# TempSensors.net
KiCad netlist of a schematic drawn in Altium Designer
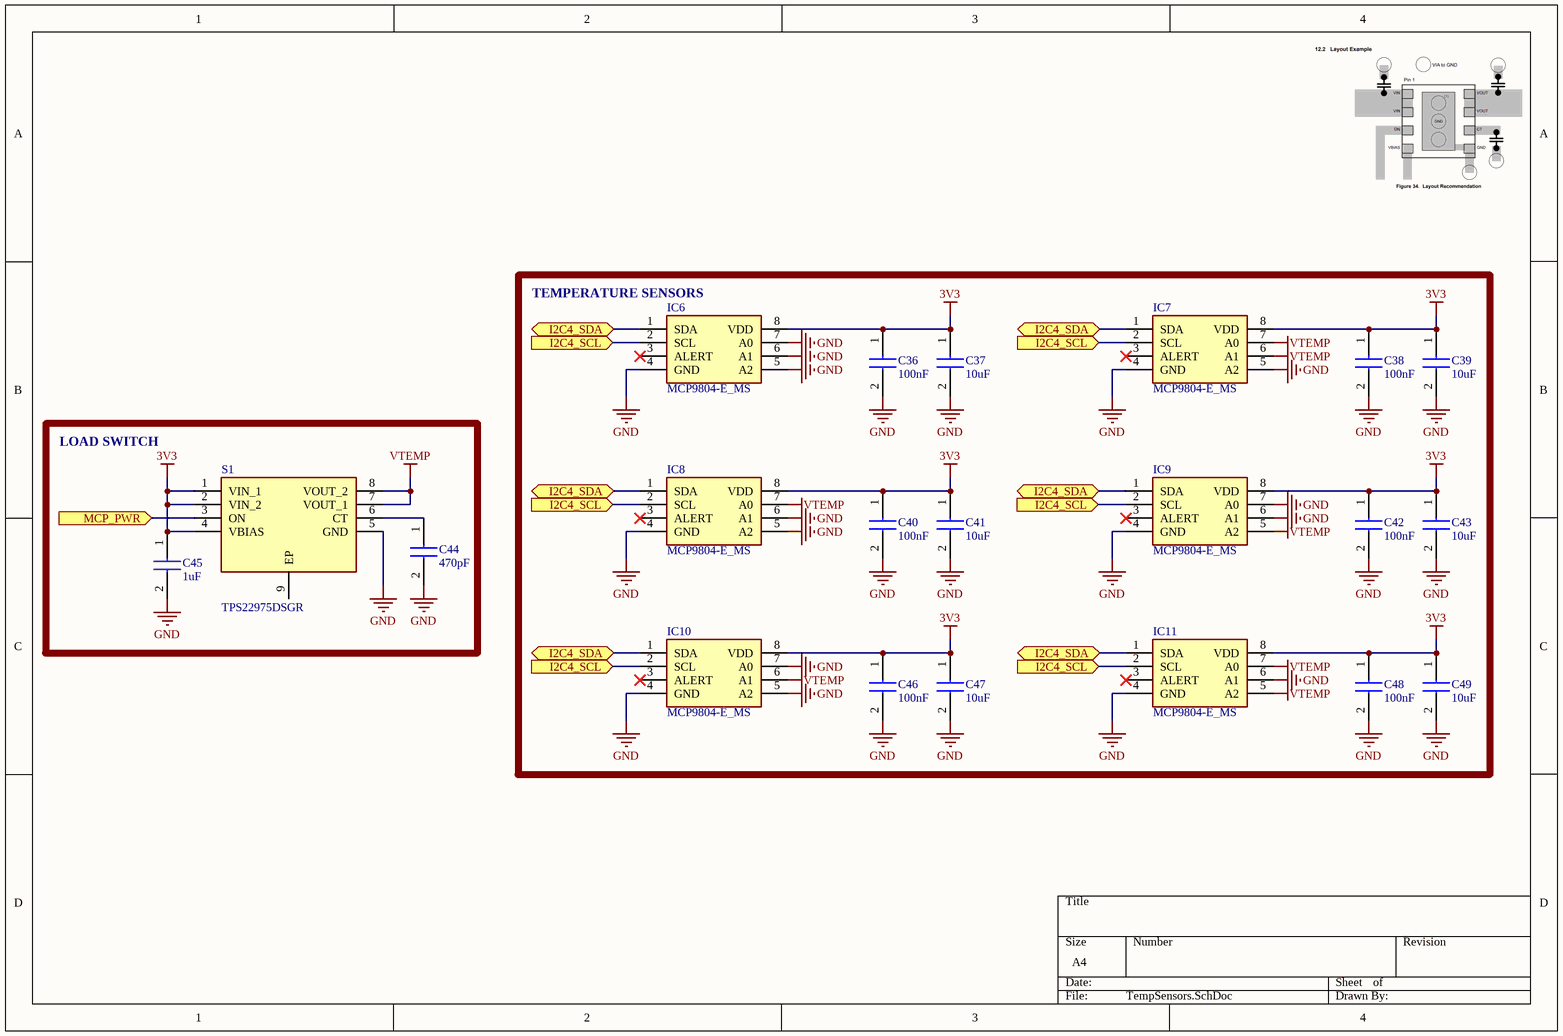
[diagram p0: TempSensors.SchDoc]

(export (version "E")
  (design (tool "Eeschema 10.0.6"))
  (components
    (comp (ref "C36")
      (value "100nF")
      (footprint "RT_IS:CAPC1608X95N")
      (description "0.1 µF ±20% 16V Ceramic Capacitor X7R 0603 (1608 Metric)")
      (fields (field (name "MANUFACTURER_PART_NUMBER") "C0603C104M4RAC7867"))
      (libsource (lib "*") (part "C0603C104M4RAC7867"))
    )
    (comp (ref "C37")
      (value "10uF")
      (footprint "RT_IS:CAPC1608X90N")
      (description "CAP CER 10UF 10V X7T 0603")
      (fields
        (field (name "MANUFACTURER_PART_NUMBER") "GRM188D71A106KA73D")
        (field (name "MOUSER PART NUMBER") "81-GRM188D71A106KA3D")
      )
      (libsource (lib "*") (part "GRM188D71A106KA73D"))
    )
    (comp (ref "C38")
      (value "100nF")
      (footprint "RT_IS:CAPC1608X95N")
      (description "0.1 µF ±20% 16V Ceramic Capacitor X7R 0603 (1608 Metric)")
      (fields (field (name "MANUFACTURER_PART_NUMBER") "C0603C104M4RAC7867"))
      (libsource (lib "*") (part "C0603C104M4RAC7867"))
    )
    (comp (ref "C39")
      (value "10uF")
      (footprint "RT_IS:CAPC1608X90N")
      (description "CAP CER 10UF 10V X7T 0603")
      (fields
        (field (name "MANUFACTURER_PART_NUMBER") "GRM188D71A106KA73D")
        (field (name "MOUSER PART NUMBER") "81-GRM188D71A106KA3D")
      )
      (libsource (lib "*") (part "GRM188D71A106KA73D"))
    )
    (comp (ref "C40")
      (value "100nF")
      (footprint "RT_IS:CAPC1608X95N")
      (description "0.1 µF ±20% 16V Ceramic Capacitor X7R 0603 (1608 Metric)")
      (fields (field (name "MANUFACTURER_PART_NUMBER") "C0603C104M4RAC7867"))
      (libsource (lib "*") (part "C0603C104M4RAC7867"))
    )
    (comp (ref "C41")
      (value "10uF")
      (footprint "RT_IS:CAPC1608X90N")
      (description "CAP CER 10UF 10V X7T 0603")
      (fields
        (field (name "MANUFACTURER_PART_NUMBER") "GRM188D71A106KA73D")
        (field (name "MOUSER PART NUMBER") "81-GRM188D71A106KA3D")
      )
      (libsource (lib "*") (part "GRM188D71A106KA73D"))
    )
    (comp (ref "C42")
      (value "100nF")
      (footprint "RT_IS:CAPC1608X95N")
      (description "0.1 µF ±20% 16V Ceramic Capacitor X7R 0603 (1608 Metric)")
      (fields (field (name "MANUFACTURER_PART_NUMBER") "C0603C104M4RAC7867"))
      (libsource (lib "*") (part "C0603C104M4RAC7867"))
    )
    (comp (ref "C43")
      (value "10uF")
      (footprint "RT_IS:CAPC1608X90N")
      (description "CAP CER 10UF 10V X7T 0603")
      (fields
        (field (name "MANUFACTURER_PART_NUMBER") "GRM188D71A106KA73D")
        (field (name "MOUSER PART NUMBER") "81-GRM188D71A106KA3D")
      )
      (libsource (lib "*") (part "GRM188D71A106KA73D"))
    )
    (comp (ref "C44")
      (value "470pF")
      (footprint "RT_IS:CAPC1608X87N")
      (description "CAP CER 470PF 50V X7R 0603")
      (fields (field (name "MANUFACTURER_PART_NUMBER") "0603B471K500CT"))
      (libsource (lib "*") (part "0603B471K500CT"))
    )
    (comp (ref "C45")
      (value "1uF")
      (footprint "RT_IS:CAPC1608X90N")
      (description "1 µF ±10% 25V Ceramic Capacitor X5R 0603 (1608 Metric)")
      (fields
        (field (name "MANUFACTURER_PART_NUMBER") "CL10A105KA8NNNC")
        (field (name "MOUSER PART NUMBER") "187-CL10A105KA8NNNC")
      )
      (libsource (lib "*") (part "CL10A105KA8NNNC"))
    )
    (comp (ref "C46")
      (value "100nF")
      (footprint "RT_IS:CAPC1608X95N")
      (description "0.1 µF ±20% 16V Ceramic Capacitor X7R 0603 (1608 Metric)")
      (fields (field (name "MANUFACTURER_PART_NUMBER") "C0603C104M4RAC7867"))
      (libsource (lib "*") (part "C0603C104M4RAC7867"))
    )
    (comp (ref "C47")
      (value "10uF")
      (footprint "RT_IS:CAPC1608X90N")
      (description "CAP CER 10UF 10V X7T 0603")
      (fields
        (field (name "MANUFACTURER_PART_NUMBER") "GRM188D71A106KA73D")
        (field (name "MOUSER PART NUMBER") "81-GRM188D71A106KA3D")
      )
      (libsource (lib "*") (part "GRM188D71A106KA73D"))
    )
    (comp (ref "C48")
      (value "100nF")
      (footprint "RT_IS:CAPC1608X95N")
      (description "0.1 µF ±20% 16V Ceramic Capacitor X7R 0603 (1608 Metric)")
      (fields (field (name "MANUFACTURER_PART_NUMBER") "C0603C104M4RAC7867"))
      (libsource (lib "*") (part "C0603C104M4RAC7867"))
    )
    (comp (ref "C49")
      (value "10uF")
      (footprint "RT_IS:CAPC1608X90N")
      (description "CAP CER 10UF 10V X7T 0603")
      (fields
        (field (name "MANUFACTURER_PART_NUMBER") "GRM188D71A106KA73D")
        (field (name "MOUSER PART NUMBER") "81-GRM188D71A106KA3D")
      )
      (libsource (lib "*") (part "GRM188D71A106KA73D"))
    )
    (comp (ref "IC6")
      (value "MCP9804-E_MS")
      (footprint "RT_IS:SOP65P490X110-8N")
      (description "Temperature Sensor Digital, Local -40°C ~ 125°C 10 b 8-MSOP")
      (fields
        (field (name "MANUFACTURER_PART_NUMBER") "MCP9804-E/MS")
        (field (name "MOUSER PART NUMBER") "579-MCP9804-E/MS")
      )
      (libsource (lib "*") (part "MCP9804-E_MS"))
    )
    (comp (ref "IC7")
      (value "MCP9804-E_MS")
      (footprint "RT_IS:SOP65P490X110-8N")
      (description "Temperature Sensor Digital, Local -40°C ~ 125°C 10 b 8-MSOP")
      (fields
        (field (name "MANUFACTURER_PART_NUMBER") "MCP9804-E/MS")
        (field (name "MOUSER PART NUMBER") "579-MCP9804-E/MS")
      )
      (libsource (lib "*") (part "MCP9804-E_MS"))
    )
    (comp (ref "IC8")
      (value "MCP9804-E_MS")
      (footprint "RT_IS:SOP65P490X110-8N")
      (description "Temperature Sensor Digital, Local -40°C ~ 125°C 10 b 8-MSOP")
      (fields
        (field (name "MANUFACTURER_PART_NUMBER") "MCP9804-E/MS")
        (field (name "MOUSER PART NUMBER") "579-MCP9804-E/MS")
      )
      (libsource (lib "*") (part "MCP9804-E_MS"))
    )
    (comp (ref "IC9")
      (value "MCP9804-E_MS")
      (footprint "RT_IS:SOP65P490X110-8N")
      (description "Temperature Sensor Digital, Local -40°C ~ 125°C 10 b 8-MSOP")
      (fields
        (field (name "MANUFACTURER_PART_NUMBER") "MCP9804-E/MS")
        (field (name "MOUSER PART NUMBER") "579-MCP9804-E/MS")
      )
      (libsource (lib "*") (part "MCP9804-E_MS"))
    )
    (comp (ref "IC10")
      (value "MCP9804-E_MS")
      (footprint "RT_IS:SOP65P490X110-8N")
      (description "Temperature Sensor Digital, Local -40°C ~ 125°C 10 b 8-MSOP")
      (fields
        (field (name "MANUFACTURER_PART_NUMBER") "MCP9804-E/MS")
        (field (name "MOUSER PART NUMBER") "579-MCP9804-E/MS")
      )
      (libsource (lib "*") (part "MCP9804-E_MS"))
    )
    (comp (ref "IC11")
      (value "MCP9804-E_MS")
      (footprint "RT_IS:SOP65P490X110-8N")
      (description "Temperature Sensor Digital, Local -40°C ~ 125°C 10 b 8-MSOP")
      (fields
        (field (name "MANUFACTURER_PART_NUMBER") "MCP9804-E/MS")
        (field (name "MOUSER PART NUMBER") "579-MCP9804-E/MS")
      )
      (libsource (lib "*") (part "MCP9804-E_MS"))
    )
    (comp (ref "S1")
      (value "TPS22975DSGR")
      (footprint "RT_IS:SON50P200X200X80-9N")
      (description "Power Switch/Driver 1:1 N-Channel 6A 8-WSON (2x2)")
      (fields (field (name "MOUSER PART NUMBER") "595-TPS22975DSGR"))
      (libsource (lib "*") (part "TPS22975DSGR"))
    )
  )
  (nets
    (net (code "1") (name "/I2C4_SCL") (class "Default")
      (node (ref "IC10") (pin "2") (pinfunction "SCL_2") (pintype "passive"))
      (node (ref "IC11") (pin "2") (pinfunction "SCL_2") (pintype "passive"))
      (node (ref "IC6") (pin "2") (pinfunction "SCL_2") (pintype "passive"))
      (node (ref "IC7") (pin "2") (pinfunction "SCL_2") (pintype "passive"))
      (node (ref "IC8") (pin "2") (pinfunction "SCL_2") (pintype "passive"))
    )
    (net (code "2") (name "/I2C4_SDA") (class "Default")
      (node (ref "IC10") (pin "1") (pinfunction "SDA_1") (pintype "passive"))
      (node (ref "IC11") (pin "1") (pinfunction "SDA_1") (pintype "passive"))
      (node (ref "IC6") (pin "1") (pinfunction "SDA_1") (pintype "passive"))
      (node (ref "IC7") (pin "1") (pinfunction "SDA_1") (pintype "passive"))
      (node (ref "IC8") (pin "1") (pinfunction "SDA_1") (pintype "passive"))
    )
    (net (code "3") (name "/MCP_PWR") (class "Default")
      (node (ref "S1") (pin "3") (pinfunction "ON_3") (pintype "passive"))
    )
    (net (code "4") (name "3V3") (class "Default")
      (node (ref "C36") (pin "1") (pinfunction "1_1") (pintype "passive"))
      (node (ref "C37") (pin "1") (pinfunction "1_1") (pintype "passive"))
      (node (ref "C38") (pin "1") (pinfunction "1_1") (pintype "passive"))
      (node (ref "C39") (pin "1") (pinfunction "1_1") (pintype "passive"))
      (node (ref "C40") (pin "1") (pinfunction "1_1") (pintype "passive"))
      (node (ref "C41") (pin "1") (pinfunction "1_1") (pintype "passive"))
      (node (ref "C42") (pin "1") (pinfunction "1_1") (pintype "passive"))
      (node (ref "C43") (pin "1") (pinfunction "1_1") (pintype "passive"))
      (node (ref "C45") (pin "1") (pinfunction "1_1") (pintype "passive"))
      (node (ref "C46") (pin "1") (pinfunction "1_1") (pintype "passive"))
      (node (ref "C47") (pin "1") (pinfunction "1_1") (pintype "passive"))
      (node (ref "C48") (pin "1") (pinfunction "1_1") (pintype "passive"))
      (node (ref "C49") (pin "1") (pinfunction "1_1") (pintype "passive"))
      (node (ref "IC10") (pin "8") (pinfunction "VDD_8") (pintype "passive"))
      (node (ref "IC11") (pin "8") (pinfunction "VDD_8") (pintype "passive"))
      (node (ref "IC6") (pin "8") (pinfunction "VDD_8") (pintype "passive"))
      (node (ref "IC7") (pin "8") (pinfunction "VDD_8") (pintype "passive"))
      (node (ref "IC8") (pin "8") (pinfunction "VDD_8") (pintype "passive"))
      (node (ref "IC9") (pin "8") (pinfunction "VDD_8") (pintype "passive"))
      (node (ref "S1") (pin "1") (pinfunction "VIN_1_1") (pintype "passive"))
      (node (ref "S1") (pin "2") (pinfunction "VIN_2_2") (pintype "passive"))
      (node (ref "S1") (pin "4") (pinfunction "VBIAS_4") (pintype "passive"))
    )
    (net (code "5") (name "GND") (class "Default")
      (node (ref "C36") (pin "2") (pinfunction "2_2") (pintype "passive"))
      (node (ref "C37") (pin "2") (pinfunction "2_2") (pintype "passive"))
      (node (ref "C38") (pin "2") (pinfunction "2_2") (pintype "passive"))
      (node (ref "C39") (pin "2") (pinfunction "2_2") (pintype "passive"))
      (node (ref "C40") (pin "2") (pinfunction "2_2") (pintype "passive"))
      (node (ref "C41") (pin "2") (pinfunction "2_2") (pintype "passive"))
      (node (ref "C42") (pin "2") (pinfunction "2_2") (pintype "passive"))
      (node (ref "C43") (pin "2") (pinfunction "2_2") (pintype "passive"))
      (node (ref "C44") (pin "2") (pinfunction "2_2") (pintype "passive"))
      (node (ref "C45") (pin "2") (pinfunction "2_2") (pintype "passive"))
      (node (ref "C46") (pin "2") (pinfunction "2_2") (pintype "passive"))
      (node (ref "C47") (pin "2") (pinfunction "2_2") (pintype "passive"))
      (node (ref "C48") (pin "2") (pinfunction "2_2") (pintype "passive"))
      (node (ref "C49") (pin "2") (pinfunction "2_2") (pintype "passive"))
      (node (ref "IC10") (pin "4") (pinfunction "GND_4") (pintype "passive"))
      (node (ref "IC10") (pin "5") (pinfunction "A2_5") (pintype "passive"))
      (node (ref "IC10") (pin "7") (pinfunction "A0_7") (pintype "passive"))
      (node (ref "IC11") (pin "4") (pinfunction "GND_4") (pintype "passive"))
      (node (ref "IC11") (pin "6") (pinfunction "A1_6") (pintype "passive"))
      (node (ref "IC6") (pin "4") (pinfunction "GND_4") (pintype "passive"))
      (node (ref "IC6") (pin "5") (pinfunction "A2_5") (pintype "passive"))
      (node (ref "IC6") (pin "6") (pinfunction "A1_6") (pintype "passive"))
      (node (ref "IC6") (pin "7") (pinfunction "A0_7") (pintype "passive"))
      (node (ref "IC7") (pin "4") (pinfunction "GND_4") (pintype "passive"))
      (node (ref "IC7") (pin "5") (pinfunction "A2_5") (pintype "passive"))
      (node (ref "IC8") (pin "4") (pinfunction "GND_4") (pintype "passive"))
      (node (ref "IC8") (pin "5") (pinfunction "A2_5") (pintype "passive"))
      (node (ref "IC8") (pin "6") (pinfunction "A1_6") (pintype "passive"))
      (node (ref "IC9") (pin "4") (pinfunction "GND_4") (pintype "passive"))
      (node (ref "IC9") (pin "6") (pinfunction "A1_6") (pintype "passive"))
      (node (ref "IC9") (pin "7") (pinfunction "A0_7") (pintype "passive"))
      (node (ref "S1") (pin "5") (pinfunction "GND_5") (pintype "passive"))
    )
    (net (code "6") (name "Net-(S1-CT)") (class "Default")
      (node (ref "C44") (pin "1") (pinfunction "1_1") (pintype "passive"))
      (node (ref "S1") (pin "6") (pinfunction "CT_6") (pintype "passive"))
    )
    (net (code "7") (name "VTEMP") (class "Default")
      (node (ref "IC10") (pin "6") (pinfunction "A1_6") (pintype "passive"))
      (node (ref "IC11") (pin "5") (pinfunction "A2_5") (pintype "passive"))
      (node (ref "IC11") (pin "7") (pinfunction "A0_7") (pintype "passive"))
      (node (ref "IC7") (pin "6") (pinfunction "A1_6") (pintype "passive"))
      (node (ref "IC7") (pin "7") (pinfunction "A0_7") (pintype "passive"))
      (node (ref "IC8") (pin "7") (pinfunction "A0_7") (pintype "passive"))
      (node (ref "IC9") (pin "5") (pinfunction "A2_5") (pintype "passive"))
      (node (ref "S1") (pin "7") (pinfunction "VOUT_1_7") (pintype "passive"))
      (node (ref "S1") (pin "8") (pinfunction "VOUT_2_8") (pintype "passive"))
    )
    (net (code "8") (name "unconnected-(IC6-ALERT-Pad3)") (class "Default")
      (node (ref "IC6") (pin "3") (pinfunction "ALERT_3") (pintype "passive+no_connect"))
    )
    (net (code "9") (name "unconnected-(IC7-ALERT-Pad3)") (class "Default")
      (node (ref "IC7") (pin "3") (pinfunction "ALERT_3") (pintype "passive+no_connect"))
    )
    (net (code "10") (name "unconnected-(IC8-ALERT-Pad3)") (class "Default")
      (node (ref "IC8") (pin "3") (pinfunction "ALERT_3") (pintype "passive+no_connect"))
    )
    (net (code "11") (name "unconnected-(IC9-ALERT-Pad3)") (class "Default")
      (node (ref "IC9") (pin "3") (pinfunction "ALERT_3") (pintype "passive+no_connect"))
    )
    (net (code "12") (name "unconnected-(IC9-SCL-Pad2)") (class "Default")
      (node (ref "IC9") (pin "2") (pinfunction "SCL_2") (pintype "passive"))
    )
    (net (code "13") (name "unconnected-(IC9-SDA-Pad1)") (class "Default")
      (node (ref "IC9") (pin "1") (pinfunction "SDA_1") (pintype "passive"))
    )
    (net (code "14") (name "unconnected-(IC10-ALERT-Pad3)") (class "Default")
      (node (ref "IC10") (pin "3") (pinfunction "ALERT_3") (pintype "passive+no_connect"))
    )
    (net (code "15") (name "unconnected-(IC11-ALERT-Pad3)") (class "Default")
      (node (ref "IC11") (pin "3") (pinfunction "ALERT_3") (pintype "passive+no_connect"))
    )
    (net (code "16") (name "unconnected-(S1-EP-Pad9)") (class "Default")
      (node (ref "S1") (pin "9") (pinfunction "EP_9") (pintype "passive"))
    )
  )
)
